# 18650M.net
KiCad netlist of a schematic drawn in Altium Designer
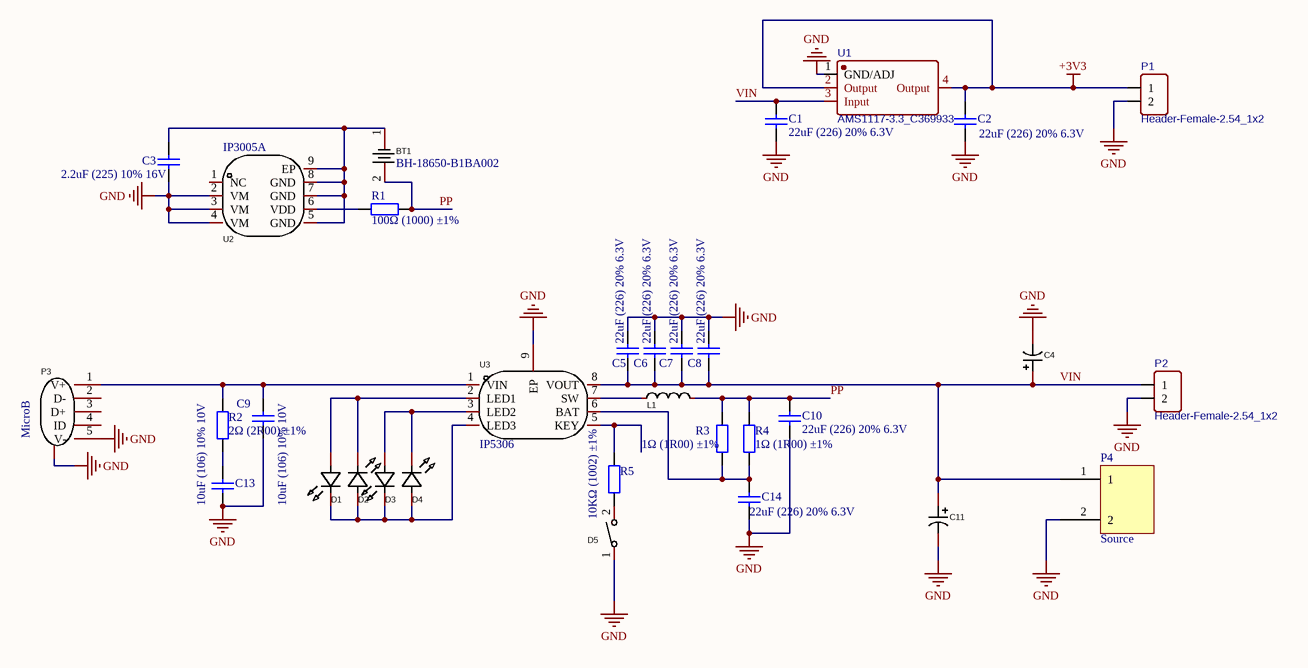
[diagram p0: 18650M.SchDoc]

(export (version "E")
  (design (tool "Eeschema 10.0.6"))
  (components
    (comp (ref "BT1")
      (value "BH-18650-B1BA002")
      (footprint "BATTERY-SMD_18650-1S-L77.1-W20.7-1")
      (fields (field (name "MANUFACTURER") "MYOUNG(美阳)"))
      (libsource (lib "电源充放管理") (part "BH-18650-B1BA002"))
    )
    (comp (ref "C1")
      (value "22uF (226) 20% 6.3V")
      (footprint "0603_C")
      (description "贴片电容")
      (libsource (lib "Cap") (part "0603 22uF (226) 20% 6.3V"))
    )
    (comp (ref "C2")
      (value "22uF (226) 20% 6.3V")
      (footprint "0603_C")
      (description "贴片电容")
      (libsource (lib "Cap") (part "0603 22uF (226) 20% 6.3V"))
    )
    (comp (ref "C3")
      (value "2.2uF (225) 10% 16V")
      (footprint "0603_C")
      (description "贴片电容")
      (libsource (lib "Cap") (part "0603 2.2uF (225) 10% 16V"))
    )
    (comp (ref "C4")
      (value "ULR107M1CE08TUX0CR")
      (footprint "CAP-TH_BD6.3-P2.50-D0.6-FD")
      (fields (field (name "MANUFACTURER") "MAN YUE(万裕科技)") (field (name "TOLERANCE") "±20%"))
      (libsource (lib "Stm32Basic") (part "100uF/16V"))
    )
    (comp (ref "C5")
      (value "22uF (226) 20% 6.3V")
      (footprint "0603_C")
      (description "贴片电容")
      (libsource (lib "Cap") (part "0603 22uF (226) 20% 6.3V"))
    )
    (comp (ref "C6")
      (value "22uF (226) 20% 6.3V")
      (footprint "0603_C")
      (description "贴片电容")
      (libsource (lib "Cap") (part "0603 22uF (226) 20% 6.3V"))
    )
    (comp (ref "C7")
      (value "22uF (226) 20% 6.3V")
      (footprint "0603_C")
      (description "贴片电容")
      (libsource (lib "Cap") (part "0603 22uF (226) 20% 6.3V"))
    )
    (comp (ref "C8")
      (value "22uF (226) 20% 6.3V")
      (footprint "0603_C")
      (description "贴片电容")
      (libsource (lib "Cap") (part "0603 22uF (226) 20% 6.3V"))
    )
    (comp (ref "C9")
      (value "10uF (106) 10% 10V")
      (footprint "0603_C")
      (description "贴片电容")
      (libsource (lib "Cap") (part "0603 10uF (106) 10% 10V"))
    )
    (comp (ref "C10")
      (value "22uF (226) 20% 6.3V")
      (footprint "0603_C")
      (description "贴片电容")
      (libsource (lib "Cap") (part "0603 22uF (226) 20% 6.3V"))
    )
    (comp (ref "C11")
      (value "ULR107M1CE08TUX0CR")
      (footprint "CAP-TH_BD6.3-P2.50-D0.6-FD")
      (fields (field (name "MANUFACTURER") "MAN YUE(万裕科技)") (field (name "TOLERANCE") "±20%"))
      (libsource (lib "Stm32Basic") (part "100uF/16V"))
    )
    (comp (ref "C13")
      (value "10uF (106) 10% 10V")
      (footprint "0603_C")
      (description "贴片电容")
      (libsource (lib "Cap") (part "0603 10uF (106) 10% 10V"))
    )
    (comp (ref "C14")
      (value "22uF (226) 20% 6.3V")
      (footprint "0603_C")
      (description "贴片电容")
      (libsource (lib "Cap") (part "0603 22uF (226) 20% 6.3V"))
    )
    (comp (ref "D1")
      (value "RF-BGB170TS-CB-E0")
      (footprint "LED0805-RD_BLUE")
      (fields (field (name "MANUFACTURER") "Refond(瑞丰)"))
      (libsource (lib "Stm32Basic") (part "RF-BGB170TS-CB-E0"))
    )
    (comp (ref "D2")
      (value "RF-BGB170TS-CB-E0")
      (footprint "LED0805-RD_BLUE")
      (fields (field (name "MANUFACTURER") "Refond(瑞丰)"))
      (libsource (lib "Stm32Basic") (part "RF-BGB170TS-CB-E0"))
    )
    (comp (ref "D3")
      (value "RF-BGB170TS-CB-E0")
      (footprint "LED0805-RD_BLUE")
      (fields (field (name "MANUFACTURER") "Refond(瑞丰)"))
      (libsource (lib "Stm32Basic") (part "RF-BGB170TS-CB-E0"))
    )
    (comp (ref "D4")
      (value "RF-BGB170TS-CB-E0")
      (footprint "LED0805-RD_BLUE")
      (fields (field (name "MANUFACTURER") "Refond(瑞丰)"))
      (libsource (lib "Stm32Basic") (part "RF-BGB170TS-CB-E0"))
    )
    (comp (ref "D5")
      (value "TS342A2P-WZ")
      (footprint "SW-SMD_L4.0-W2.9-LS5.0")
      (fields (field (name "MANUFACTURER") "SHOU HAN(首韩)"))
      (libsource (lib "Stm32Basic") (part "TS342A2P-WZ"))
    )
    (comp (ref "L1")
      (value "NBMC0630N-1R0M")
      (footprint "IND-SMD_L7.4-W6.6")
      (fields (field (name "MANUFACTURER") "MINGSTAR(登壹)") (field (name "TOLERANCE") "±20%"))
      (libsource (lib "电源充放管理") (part "NBMC0630N-1R0M"))
    )
    (comp (ref "P1")
      (value "Header-Female-2.54_1x2")
      (footprint "HDR-TH_2P-P2.54-V-F")
      (fields
        (field (name "BOM_MANUFACTURER PART") "2.54-1*2PFemale")
        (field (name "BOM_SUPPLIER PART") "C49661")
      )
      (libsource (lib "Schlib1") (part "Header-Female-2.54_1x2"))
    )
    (comp (ref "P2")
      (value "Header-Female-2.54_1x2")
      (footprint "HDR-TH_2P-P2.54-V-F")
      (fields
        (field (name "BOM_MANUFACTURER PART") "2.54-1*2PFemale")
        (field (name "BOM_SUPPLIER PART") "C49661")
      )
      (libsource (lib "Schlib1") (part "Header-Female-2.54_1x2"))
    )
    (comp (ref "P3")
      (value "MicroB")
      (footprint "MICRO-USB-SMD_5P-P0.65-H-F_C10418")
      (fields (field (name "MANUFACTURER") "精拓金") (field (name "MANUFACTURER PART") "920-E52A2021S10100"))
      (libsource (lib "Stm32Basic") (part "MicroB"))
    )
    (comp (ref "P4") (value "Source") (footprint "XT30-M") (libsource (lib "Schlib1") (part "XT30")))
    (comp (ref "R1")
      (value "100Ω (1000) ±1%")
      (footprint "0603_R")
      (description "贴片电阻")
      (libsource (lib "RES") (part "0603 100Ω (1000) 1%"))
    )
    (comp (ref "R2")
      (value "2Ω (2R00) ±1%")
      (footprint "0603_R")
      (description "贴片电阻")
      (libsource (lib "RES") (part "0603 2Ω (2R00) 1%"))
    )
    (comp (ref "R3")
      (value "1Ω (1R00) ±1%")
      (footprint "0603_R")
      (description "贴片电阻")
      (libsource (lib "RES") (part "0603 1Ω (1R00) 1%"))
    )
    (comp (ref "R4")
      (value "1Ω (1R00) ±1%")
      (footprint "0603_R")
      (description "贴片电阻")
      (libsource (lib "RES") (part "0603 1Ω (1R00) 1%"))
    )
    (comp (ref "R5")
      (value "10KΩ (1002) ±1%")
      (footprint "0603_R")
      (description "贴片电阻")
      (libsource (lib "RES") (part "0603 10KΩ (1002) 1%"))
    )
    (comp (ref "U1")
      (value "AMS1117-3.3_C369933")
      (footprint "SOT-223-4_L6.5-W3.5-P2.30-LS7.0-BR")
      (fields
        (field (name "BOM_SUPPLIER PART") "C369933")
        (field (name "BOM_MANUFACTURER PART") "AMS1117-3.3")
        (field (name "CONTRIBUTOR") "LCSC")
      )
      (libsource (lib "Schlib1") (part "AMS1117-3.3_C369933"))
    )
    (comp (ref "U2")
      (value "IP3005A")
      (footprint "ESOP-8_L4.9-W3.9-P1.27-LS6.0-BL-EP")
      (fields (field (name "MANUFACTURER") "INJOINIC(英集芯)"))
      (libsource (lib "电源充放管理") (part "IP3005A"))
    )
    (comp (ref "U3")
      (value "IP5306")
      (footprint "ESOP-8_L4.9-W3.9-P1.27-LS6.0-BL-EP")
      (fields (field (name "MANUFACTURER") "INJOINIC(英集芯)"))
      (libsource (lib "电源充放管理") (part "IP5306"))
    )
  )
  (nets
    (net (code "1") (name "+3V3") (class "Default")
      (node (ref "C2") (pin "2") (pinfunction "2_2") (pintype "passive"))
      (node (ref "P1") (pin "1") (pinfunction "1_1") (pintype "passive"))
      (node (ref "U1") (pin "2") (pinfunction "Output_2") (pintype "passive"))
      (node (ref "U1") (pin "4") (pinfunction "Output_4") (pintype "passive"))
    )
    (net (code "2") (name "/PP") (class "Default")
      (node (ref "BT1") (pin "2") (pinfunction "2_2") (pintype "passive"))
      (node (ref "C10") (pin "2") (pinfunction "2_2") (pintype "passive"))
      (node (ref "L1") (pin "2") (pinfunction "2_2") (pintype "passive"))
      (node (ref "R1") (pin "2") (pinfunction "2_2") (pintype "passive"))
      (node (ref "R3") (pin "2") (pinfunction "2_2") (pintype "passive"))
      (node (ref "R4") (pin "2") (pinfunction "2_2") (pintype "passive"))
    )
    (net (code "3") (name "/VIN") (class "Default")
      (node (ref "C1") (pin "2") (pinfunction "2_2") (pintype "passive"))
      (node (ref "C11") (pin "1") (pinfunction "1_1") (pintype "passive"))
      (node (ref "C4") (pin "1") (pinfunction "1_1") (pintype "passive"))
      (node (ref "C5") (pin "1") (pinfunction "1_1") (pintype "passive"))
      (node (ref "C6") (pin "1") (pinfunction "1_1") (pintype "passive"))
      (node (ref "C7") (pin "1") (pinfunction "1_1") (pintype "passive"))
      (node (ref "C8") (pin "1") (pinfunction "1_1") (pintype "passive"))
      (node (ref "P2") (pin "1") (pinfunction "1_1") (pintype "passive"))
      (node (ref "P4") (pin "1") (pinfunction "1_1") (pintype "passive"))
      (node (ref "U1") (pin "3") (pinfunction "Input_3") (pintype "passive"))
      (node (ref "U3") (pin "8") (pinfunction "VOUT_8") (pintype "passive"))
    )
    (net (code "4") (name "GND") (class "Default")
      (node (ref "C1") (pin "1") (pinfunction "1_1") (pintype "passive"))
      (node (ref "C10") (pin "1") (pinfunction "1_1") (pintype "passive"))
      (node (ref "C11") (pin "2") (pinfunction "2_2") (pintype "passive"))
      (node (ref "C13") (pin "1") (pinfunction "1_1") (pintype "passive"))
      (node (ref "C14") (pin "1") (pinfunction "1_1") (pintype "passive"))
      (node (ref "C2") (pin "1") (pinfunction "1_1") (pintype "passive"))
      (node (ref "C3") (pin "1") (pinfunction "1_1") (pintype "passive"))
      (node (ref "C4") (pin "2") (pinfunction "2_2") (pintype "passive"))
      (node (ref "C5") (pin "2") (pinfunction "2_2") (pintype "passive"))
      (node (ref "C6") (pin "2") (pinfunction "2_2") (pintype "passive"))
      (node (ref "C7") (pin "2") (pinfunction "2_2") (pintype "passive"))
      (node (ref "C8") (pin "2") (pinfunction "2_2") (pintype "passive"))
      (node (ref "C9") (pin "1") (pinfunction "1_1") (pintype "passive"))
      (node (ref "D5") (pin "1") (pinfunction "1_1") (pintype "passive"))
      (node (ref "P1") (pin "2") (pinfunction "2_2") (pintype "passive"))
      (node (ref "P2") (pin "2") (pinfunction "2_2") (pintype "passive"))
      (node (ref "P3") (pin "0") (pinfunction "MTN_0") (pintype "passive"))
      (node (ref "P3") (pin "5") (pinfunction "V-_5") (pintype "passive"))
      (node (ref "P4") (pin "2") (pinfunction "2_2") (pintype "passive"))
      (node (ref "U1") (pin "1") (pinfunction "GND/ADJ_1") (pintype "passive"))
      (node (ref "U2") (pin "2") (pinfunction "VM_2") (pintype "passive"))
      (node (ref "U2") (pin "3") (pinfunction "VM_3") (pintype "passive"))
      (node (ref "U2") (pin "4") (pinfunction "VM_4") (pintype "passive"))
      (node (ref "U3") (pin "9") (pinfunction "EP_9") (pintype "passive"))
    )
    (net (code "5") (name "Net-(C13-Pad2)") (class "Default")
      (node (ref "C13") (pin "2") (pinfunction "2_2") (pintype "passive"))
      (node (ref "R2") (pin "1") (pinfunction "1_1") (pintype "passive"))
    )
    (net (code "6") (name "Net-(D1-A)") (class "Default")
      (node (ref "D1") (pin "2") (pinfunction "A_2") (pintype "passive"))
      (node (ref "D2") (pin "1") (pinfunction "K_1") (pintype "passive"))
      (node (ref "U3") (pin "2") (pinfunction "LED1_2") (pintype "passive"))
    )
    (net (code "7") (name "Net-(D1-K)") (class "Default")
      (node (ref "D1") (pin "1") (pinfunction "K_1") (pintype "passive"))
      (node (ref "D2") (pin "2") (pinfunction "A_2") (pintype "passive"))
      (node (ref "D3") (pin "1") (pinfunction "K_1") (pintype "passive"))
      (node (ref "D4") (pin "2") (pinfunction "A_2") (pintype "passive"))
      (node (ref "U3") (pin "4") (pinfunction "LED3_4") (pintype "passive"))
    )
    (net (code "8") (name "Net-(D3-A)") (class "Default")
      (node (ref "D3") (pin "2") (pinfunction "A_2") (pintype "passive"))
      (node (ref "D4") (pin "1") (pinfunction "K_1") (pintype "passive"))
      (node (ref "U3") (pin "3") (pinfunction "LED2_3") (pintype "passive"))
    )
    (net (code "9") (name "Net-(D5-Pad2)") (class "Default")
      (node (ref "D5") (pin "2") (pinfunction "2_2") (pintype "passive"))
      (node (ref "R5") (pin "1") (pinfunction "1_1") (pintype "passive"))
    )
    (net (code "10") (name "Net-(P3-V+)") (class "Default")
      (node (ref "C9") (pin "2") (pinfunction "2_2") (pintype "passive"))
      (node (ref "P3") (pin "1") (pinfunction "V+_1") (pintype "passive"))
      (node (ref "R2") (pin "2") (pinfunction "2_2") (pintype "passive"))
      (node (ref "U3") (pin "1") (pinfunction "VIN_1") (pintype "passive"))
    )
    (net (code "11") (name "Net-(U2-EP)") (class "Default")
      (node (ref "BT1") (pin "1") (pinfunction "1_1") (pintype "passive"))
      (node (ref "C3") (pin "2") (pinfunction "2_2") (pintype "passive"))
      (node (ref "U2") (pin "5") (pinfunction "GND_5") (pintype "passive"))
      (node (ref "U2") (pin "7") (pinfunction "GND_7") (pintype "passive"))
      (node (ref "U2") (pin "8") (pinfunction "GND_8") (pintype "passive"))
      (node (ref "U2") (pin "9") (pinfunction "EP_9") (pintype "passive"))
    )
    (net (code "12") (name "Net-(U2-VDD)") (class "Default")
      (node (ref "R1") (pin "1") (pinfunction "1_1") (pintype "passive"))
      (node (ref "U2") (pin "6") (pinfunction "VDD_6") (pintype "passive"))
    )
    (net (code "13") (name "Net-(U3-BAT)") (class "Default")
      (node (ref "C14") (pin "2") (pinfunction "2_2") (pintype "passive"))
      (node (ref "R3") (pin "1") (pinfunction "1_1") (pintype "passive"))
      (node (ref "R4") (pin "1") (pinfunction "1_1") (pintype "passive"))
      (node (ref "U3") (pin "6") (pinfunction "BAT_6") (pintype "passive"))
    )
    (net (code "14") (name "Net-(U3-KEY)") (class "Default")
      (node (ref "R5") (pin "2") (pinfunction "2_2") (pintype "passive"))
      (node (ref "U3") (pin "5") (pinfunction "KEY_5") (pintype "passive"))
    )
    (net (code "15") (name "Net-(U3-SW)") (class "Default")
      (node (ref "L1") (pin "1") (pinfunction "1_1") (pintype "passive"))
      (node (ref "U3") (pin "7") (pinfunction "SW_7") (pintype "passive"))
    )
    (net (code "16") (name "unconnected-(P3-D+-Pad3)") (class "Default")
      (node (ref "P3") (pin "3") (pinfunction "D+_3") (pintype "passive"))
    )
    (net (code "17") (name "unconnected-(P3-D--Pad2)") (class "Default")
      (node (ref "P3") (pin "2") (pinfunction "D-_2") (pintype "passive"))
    )
    (net (code "18") (name "unconnected-(P3-ID-Pad4)") (class "Default")
      (node (ref "P3") (pin "4") (pinfunction "ID_4") (pintype "passive"))
    )
    (net (code "19") (name "unconnected-(U2-NC-Pad1)") (class "Default")
      (node (ref "U2") (pin "1") (pinfunction "NC_1") (pintype "passive"))
    )
  )
)
